# Encoder_robo.net
KiCad netlist of a schematic drawn in EAGLE
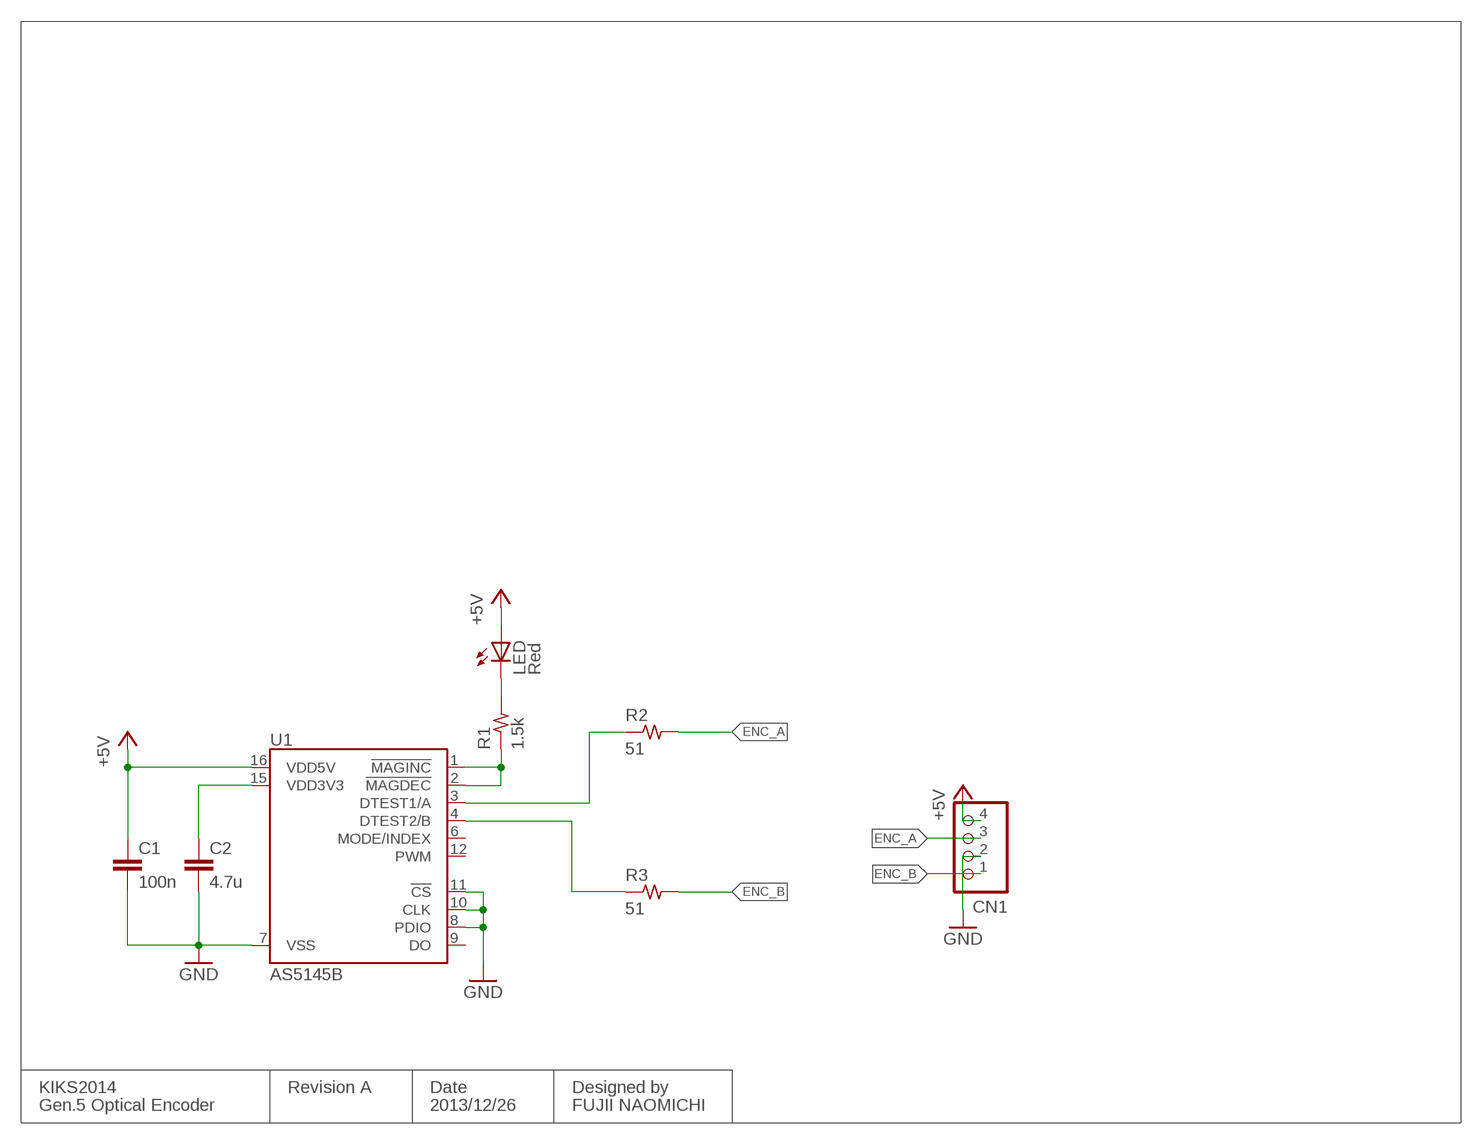
[diagram p0: schematic, sheet 1]

(export (version "E")
  (design (tool "Eeschema 10.0.6"))
  (components
    (comp (ref "C1")
      (value "100n")
      (footprint "eagle-import:1608")
      (libsource (lib "eagle-import") (part "C1608"))
    )
    (comp (ref "C2")
      (value "4.7u")
      (footprint "eagle-import:1608")
      (libsource (lib "eagle-import") (part "C1608"))
    )
    (comp (ref "CN1")
      (value "S4B-XH-A")
      (footprint "eagle-import:S4B-XH-A")
      (libsource (lib "eagle-import") (part "S4B-XH-A"))
    )
    (comp (ref "LED")
      (value "Red")
      (footprint "eagle-import:LED3MM")
      (libsource (lib "eagle-import") (part "LED3MM"))
    )
    (comp (ref "R1")
      (value "1.5k")
      (footprint "eagle-import:1608")
      (libsource (lib "eagle-import") (part "R1608"))
    )
    (comp (ref "R2")
      (value "51")
      (footprint "eagle-import:1608")
      (libsource (lib "eagle-import") (part "R1608"))
    )
    (comp (ref "R3")
      (value "51")
      (footprint "eagle-import:1608")
      (libsource (lib "eagle-import") (part "R1608"))
    )
    (comp (ref "U1")
      (value "AS5145B")
      (footprint "eagle-import:SSOP16")
      (libsource (lib "eagle-import") (part "AS5145B"))
    )
  )
  (nets
    (net (code "1") (name "+5V") (class "Default")
      (node (ref "C1") (pin "1") (pinfunction "1_1") (pintype "passive"))
      (node (ref "CN1") (pin "4") (pinfunction "4_4") (pintype "passive"))
      (node (ref "LED") (pin "A") (pinfunction "A_A") (pintype "passive"))
      (node (ref "U1") (pin "16") (pinfunction "VDD5V_16") (pintype "bidirectional"))
    )
    (net (code "2") (name "ENC_A") (class "Default")
      (node (ref "CN1") (pin "3") (pinfunction "3_3") (pintype "passive"))
      (node (ref "R2") (pin "2") (pinfunction "2_2") (pintype "passive"))
    )
    (net (code "3") (name "ENC_B") (class "Default")
      (node (ref "CN1") (pin "1") (pinfunction "1_1") (pintype "passive"))
      (node (ref "R3") (pin "2") (pinfunction "2_2") (pintype "passive"))
    )
    (net (code "4") (name "GND") (class "Default")
      (node (ref "C1") (pin "2") (pinfunction "2_2") (pintype "passive"))
      (node (ref "C2") (pin "2") (pinfunction "2_2") (pintype "passive"))
      (node (ref "CN1") (pin "2") (pinfunction "2_2") (pintype "passive"))
      (node (ref "U1") (pin "10") (pinfunction "CLK_10") (pintype "bidirectional"))
      (node (ref "U1") (pin "11") (pinfunction "~{CS}_11") (pintype "bidirectional"))
      (node (ref "U1") (pin "7") (pinfunction "VSS_7") (pintype "bidirectional"))
      (node (ref "U1") (pin "8") (pinfunction "PDIO_8") (pintype "bidirectional"))
    )
    (net (code "5") (name "Net-(LED-C)") (class "Default")
      (node (ref "LED") (pin "K") (pinfunction "C_K") (pintype "passive"))
      (node (ref "R1") (pin "2") (pinfunction "2_2") (pintype "passive"))
    )
    (net (code "6") (name "Net-(U1-DTEST1{slash}A)") (class "Default")
      (node (ref "R2") (pin "1") (pinfunction "1_1") (pintype "passive"))
      (node (ref "U1") (pin "3") (pinfunction "DTEST1/A_3") (pintype "bidirectional"))
    )
    (net (code "7") (name "Net-(U1-DTEST2{slash}B)") (class "Default")
      (node (ref "R3") (pin "1") (pinfunction "1_1") (pintype "passive"))
      (node (ref "U1") (pin "4") (pinfunction "DTEST2/B_4") (pintype "bidirectional"))
    )
    (net (code "8") (name "Net-(U1-VDD3V3)") (class "Default")
      (node (ref "C2") (pin "1") (pinfunction "1_1") (pintype "passive"))
      (node (ref "U1") (pin "15") (pinfunction "VDD3V3_15") (pintype "bidirectional"))
    )
    (net (code "9") (name "Net-(U1-~{MAGDEC})") (class "Default")
      (node (ref "R1") (pin "1") (pinfunction "1_1") (pintype "passive"))
      (node (ref "U1") (pin "1") (pinfunction "~{MAGINC}_1") (pintype "bidirectional"))
      (node (ref "U1") (pin "2") (pinfunction "~{MAGDEC}_2") (pintype "bidirectional"))
    )
    (net (code "10") (name "unconnected-(U1-DO-Pad9)") (class "Default")
      (node (ref "U1") (pin "9") (pinfunction "DO_9") (pintype "bidirectional"))
    )
    (net (code "11") (name "unconnected-(U1-MODE{slash}INDEX-Pad6)") (class "Default")
      (node (ref "U1") (pin "6") (pinfunction "MODE/INDEX_6") (pintype "bidirectional"))
    )
    (net (code "12") (name "unconnected-(U1-PWM-Pad12)") (class "Default")
      (node (ref "U1") (pin "12") (pinfunction "PWM_12") (pintype "bidirectional"))
    )
  )
)
